# SCH_Well-Pump-Protection-Controller_2025.net
KiCad netlist of a schematic drawn in EasyEDA
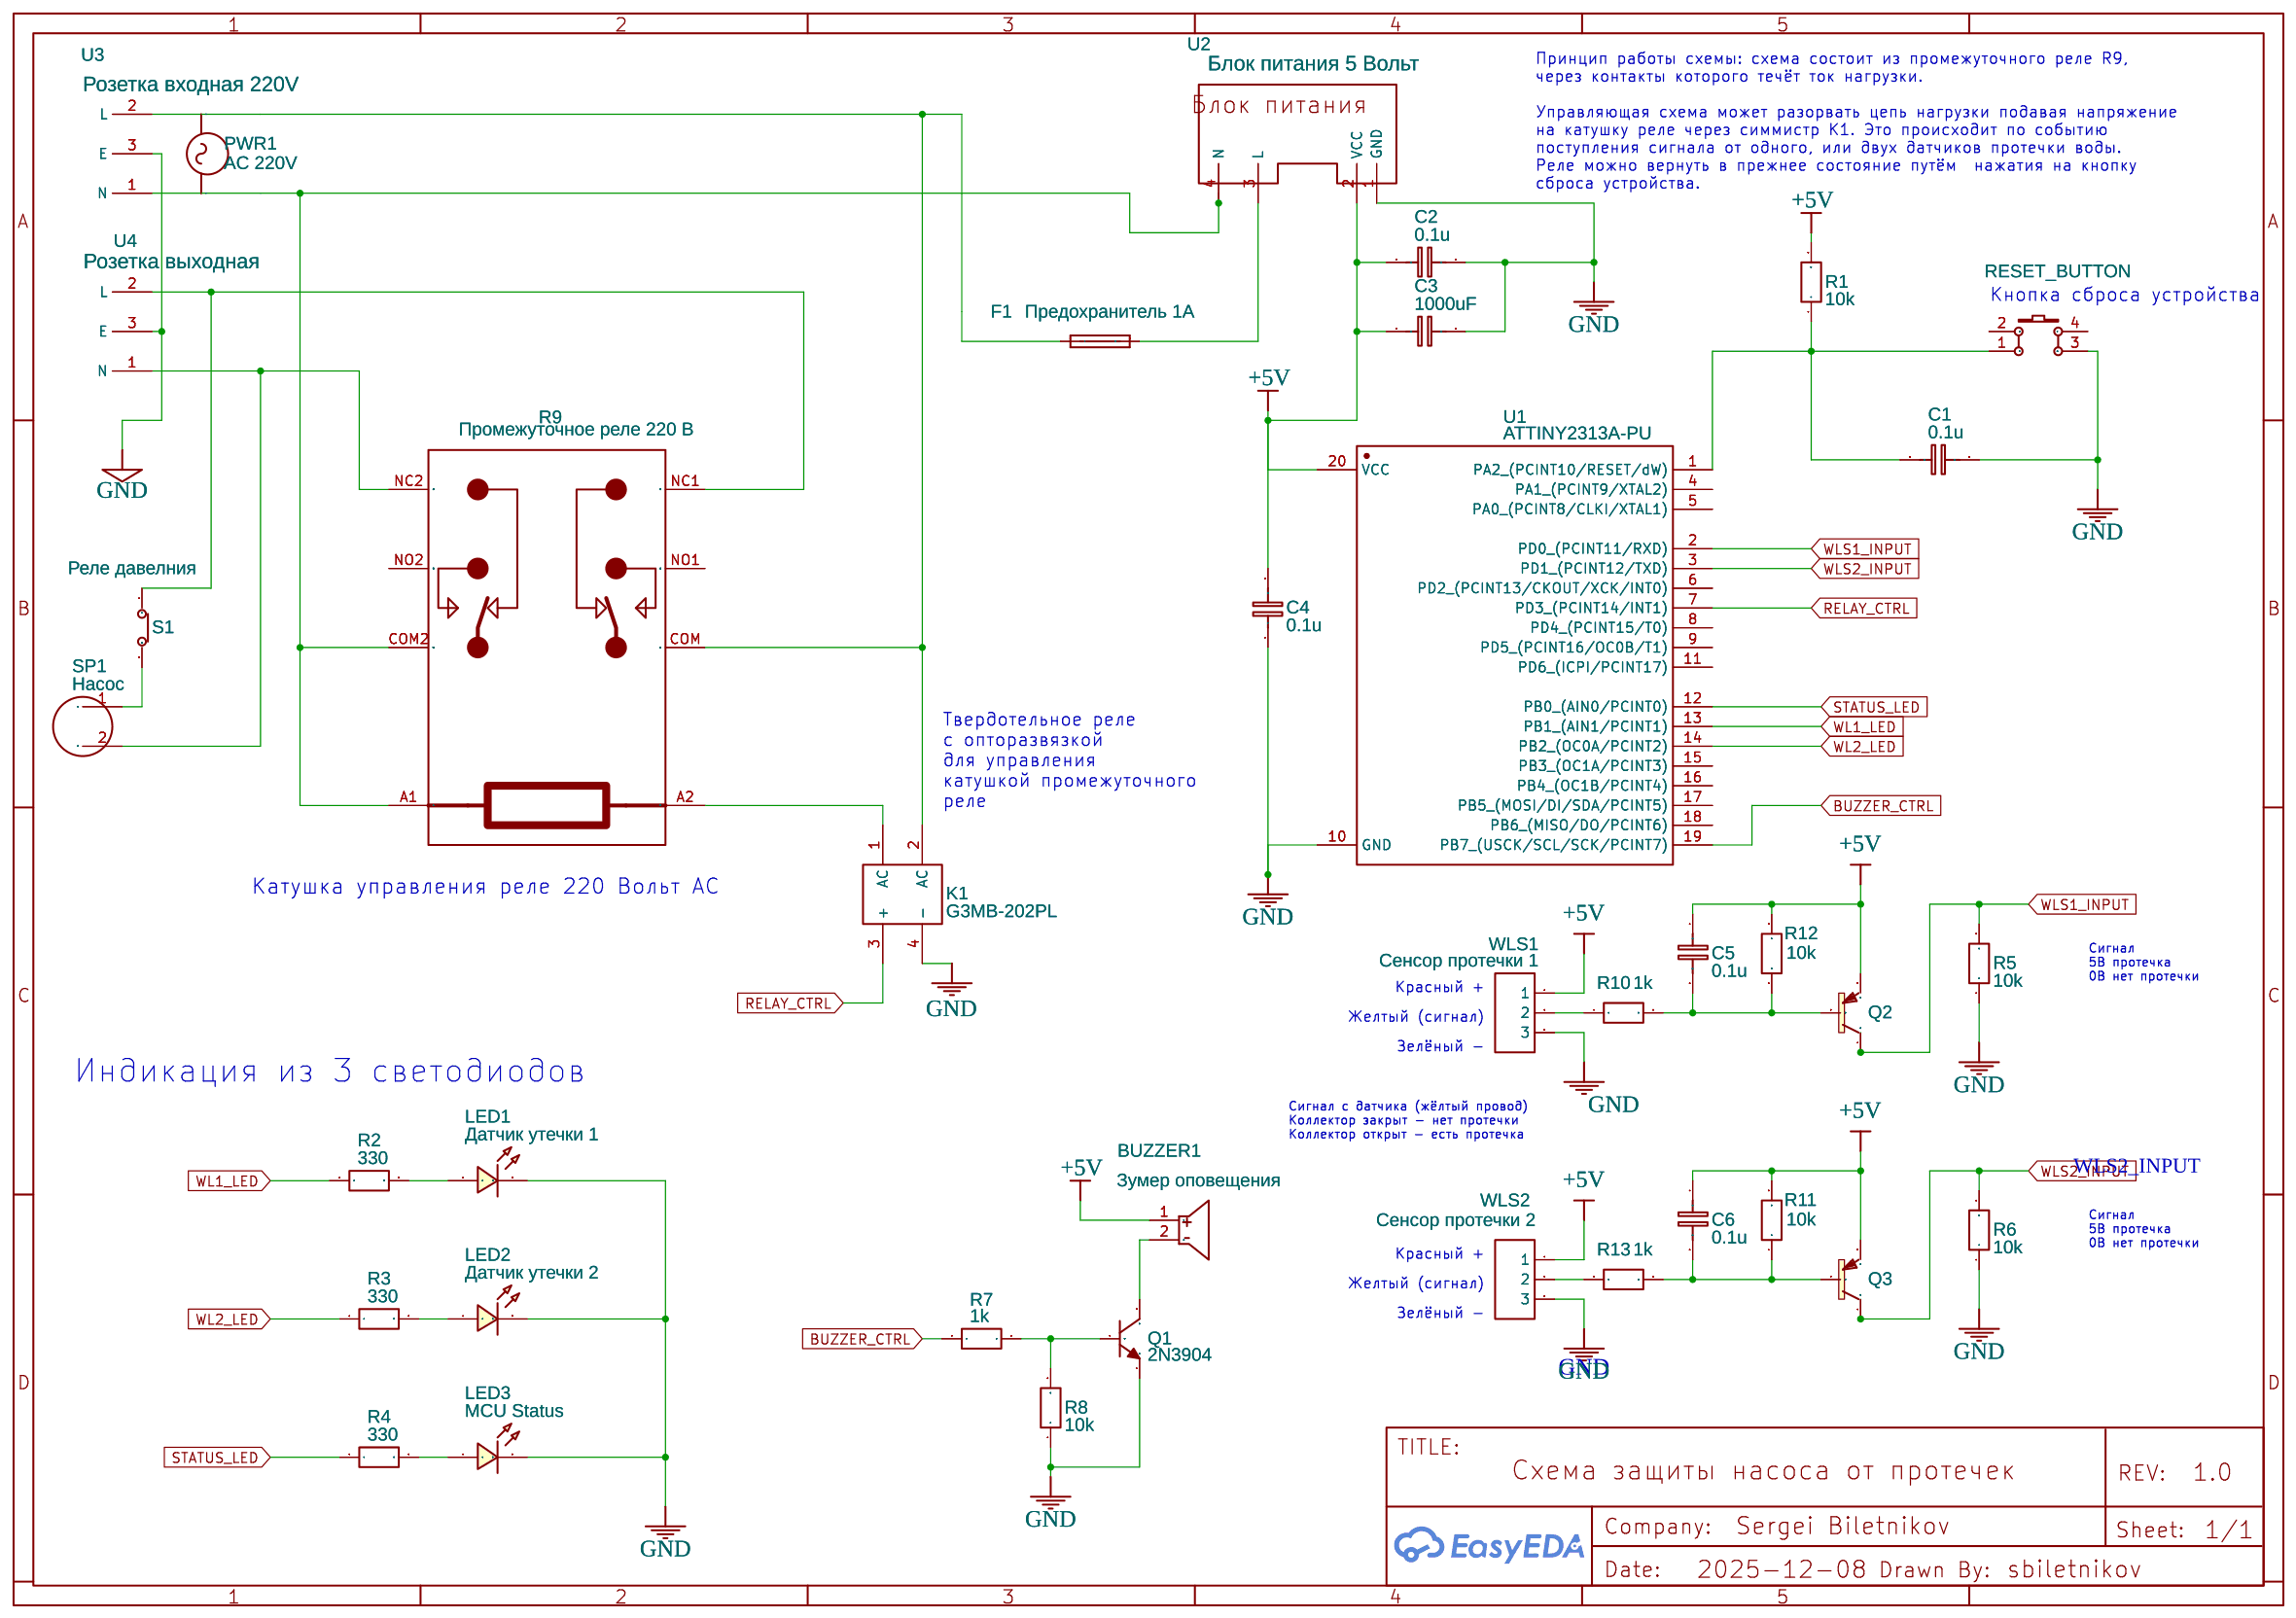
[diagram p0: schematic sheet]

(export (version "E")
  (design (tool "Eeschema 10.0.6"))
  (components
    (comp (ref "BUZZER1")
      (value "Зумер оповещения")
      (fields (field (name "Manufacturer Part") "FMQ-BUZZER2"))
      (libsource (lib "") (part "FMQ-BUZZER2"))
    )
    (comp (ref "C1") (value "0.1u") (libsource (lib "") (part "C_0603_EU")))
    (comp (ref "C2") (value "0.1u") (libsource (lib "") (part "C_0603_EU")))
    (comp (ref "C3") (value "1000uF") (libsource (lib "") (part "C_0603_EU")))
    (comp (ref "C4") (value "0.1u") (libsource (lib "") (part "C_0603_EU_1")))
    (comp (ref "C5") (value "0.1u") (libsource (lib "") (part "C_0603_EU_2")))
    (comp (ref "C6") (value "0.1u") (libsource (lib "") (part "C_0603_EU_2")))
    (comp (ref "F1") (value "Предохранитель 1А") (libsource (lib "") (part "FUSE_TERM")))
    (comp (ref "K1")
      (value "G3MB-202PL")
      (fields (field (name "Manufacturer") "OMRON(欧姆龙)"))
      (libsource (lib "") (part "G3MB-202PL"))
    )
    (comp (ref "LED1")
      (value "Датчик утечки 1")
      (fields
        (field (name "Manufacturer Part") "204-10SDRD/S530-A3-L")
        (field (name "Manufacturer") "EVERLIGHT(台湾亿光)")
      )
      (libsource (lib "") (part "LED-TH-3mm_R"))
    )
    (comp (ref "LED2")
      (value "Датчик утечки 2")
      (fields
        (field (name "Manufacturer Part") "204-10SDRD/S530-A3-L")
        (field (name "Manufacturer") "EVERLIGHT(台湾亿光)")
      )
      (libsource (lib "") (part "LED-TH-3mm_R"))
    )
    (comp (ref "LED3")
      (value "MCU Status")
      (fields
        (field (name "Manufacturer Part") "204-10SYGD/S530-E3")
        (field (name "Manufacturer") "EVERLIGHT(台湾亿光)")
      )
      (libsource (lib "") (part "LED-TH-3mm_G"))
    )
    (comp (ref "PWR1") (value "AC 220V") (libsource (lib "") (part "AC")))
    (comp (ref "Q1")
      (value "2N3904")
      (fields (field (name "Manufacturer Part") "2N3904-338") (field (name "Manufacturer") "ALJ(龙晶微)"))
      (libsource (lib "") (part "2N3904-338"))
    )
    (comp (ref "Q2") (value "2N3906PNP") (libsource (lib "") (part "2N3906PNP")))
    (comp (ref "Q3") (value "2N3906PNP") (libsource (lib "") (part "2N3906PNP")))
    (comp (ref "R1") (value "10k") (libsource (lib "") (part "R_0603_EU")))
    (comp (ref "R2") (value "330") (libsource (lib "") (part "R_0603_EU_1")))
    (comp (ref "R3") (value "330") (libsource (lib "") (part "R_0603_EU_1")))
    (comp (ref "R4") (value "330") (libsource (lib "") (part "R_0603_EU_1")))
    (comp (ref "R5") (value "10k") (libsource (lib "") (part "R_0603_EU")))
    (comp (ref "R6") (value "10k") (libsource (lib "") (part "R_0603_EU")))
    (comp (ref "R7") (value "1k") (libsource (lib "") (part "R_0603_EU_1")))
    (comp (ref "R8") (value "10k") (libsource (lib "") (part "R_0603_EU")))
    (comp (ref "R9")
      (value "Промежуточное реле 220 В")
      (fields (field (name "Manufacturer Part") "RELAY 220V AC COIL"))
      (libsource (lib "") (part "RELAY 220V AC COIL"))
    )
    (comp (ref "R10") (value "1k") (libsource (lib "") (part "R_0603_EU_1")))
    (comp (ref "R11") (value "10k") (libsource (lib "") (part "R_0603_EU")))
    (comp (ref "R12") (value "10k") (libsource (lib "") (part "R_0603_EU")))
    (comp (ref "R13") (value "1k") (libsource (lib "") (part "R_0603_EU_1")))
    (comp (ref "RESET_BUTTON")
      (value "K4-6×6_TH")
      (fields (field (name "Manufacturer Part") "K2-1102DP-E4SW-04") (field (name "Manufacturer") "韩国韩荣"))
      (libsource (lib "") (part "K4-6×6_TH"))
    )
    (comp (ref "S1")
      (value "Реле давелния")
      (fields (field (name "Manufacturer Part") "DIP switchEI-08") (field (name "Manufacturer") "DIP"))
      (libsource (lib "") (part "switch1"))
    )
    (comp (ref "SP1") (value "Насос") (libsource (lib "") (part "Pump buzz")))
    (comp (ref "U1")
      (value "ATTINY2313A-PU")
      (fields (field (name "Manufacturer") "MICROCHIP(美国微芯)"))
      (libsource (lib "") (part "ATTINY2313A-PU"))
    )
    (comp (ref "U2")
      (value "Блок питания 5 Вольт")
      (fields (field (name "Manufacturer Part") "PS-5V"))
      (libsource (lib "") (part "PowerSupply-5v"))
    )
    (comp (ref "U3")
      (value "Розетка входная 220V")
      (fields (field (name "Manufacturer Part") "IEC 320-C14"))
      (libsource (lib "") (part "Power Socket"))
    )
    (comp (ref "U4")
      (value "Розетка выходная")
      (fields (field (name "Manufacturer Part") "IEC 320-C14"))
      (libsource (lib "") (part "Power Socket"))
    )
    (comp (ref "WLS1") (value "Сенсор протечки 1") (libsource (lib "") (part "HDR-F-2.54_1x3")))
    (comp (ref "WLS2") (value "Сенсор протечки 2") (libsource (lib "") (part "HDR-F-2.54_1x3")))
  )
  (nets
    (net (code "1") (name "+5V") (class "Default")
      (node (ref "BUZZER1") (pin "1") (pinfunction "1_1") (pintype "unspecified"))
      (node (ref "C2") (pin "1") (pinfunction "1_1") (pintype "unspecified"))
      (node (ref "C3") (pin "1") (pinfunction "1_1") (pintype "unspecified"))
      (node (ref "C4") (pin "2") (pinfunction "2_2") (pintype "unspecified"))
      (node (ref "C5") (pin "1") (pinfunction "1_1") (pintype "unspecified"))
      (node (ref "C6") (pin "1") (pinfunction "1_1") (pintype "unspecified"))
      (node (ref "Q2") (pin "3") (pinfunction "E_3") (pintype "bidirectional"))
      (node (ref "Q3") (pin "3") (pinfunction "E_3") (pintype "bidirectional"))
      (node (ref "R1") (pin "2") (pinfunction "2_2") (pintype "unspecified"))
      (node (ref "R11") (pin "2") (pinfunction "2_2") (pintype "unspecified"))
      (node (ref "R12") (pin "2") (pinfunction "2_2") (pintype "unspecified"))
      (node (ref "U1") (pin "20") (pinfunction "VCC_20") (pintype "passive"))
      (node (ref "U2") (pin "2") (pinfunction "VCC_2") (pintype "unspecified"))
      (node (ref "WLS1") (pin "1") (pinfunction "1_1") (pintype "input"))
      (node (ref "WLS2") (pin "1") (pinfunction "1_1") (pintype "input"))
    )
    (net (code "2") (name "BUZZER_CTRL") (class "Default")
      (node (ref "R7") (pin "1") (pinfunction "1_1") (pintype "unspecified"))
      (node (ref "U1") (pin "19") (pinfunction "PB7_(USCK/SCL/SCK/PCINT7)_19") (pintype "bidirectional"))
    )
    (net (code "3") (name "GND") (class "Default")
      (node (ref "C1") (pin "2") (pinfunction "2_2") (pintype "unspecified"))
      (node (ref "C2") (pin "2") (pinfunction "2_2") (pintype "unspecified"))
      (node (ref "C3") (pin "2") (pinfunction "2_2") (pintype "unspecified"))
      (node (ref "C4") (pin "1") (pinfunction "1_1") (pintype "unspecified"))
      (node (ref "K1") (pin "4") (pinfunction "-_4") (pintype "unspecified"))
      (node (ref "LED1") (pin "2") (pinfunction "2_2") (pintype "unspecified"))
      (node (ref "LED2") (pin "2") (pinfunction "2_2") (pintype "unspecified"))
      (node (ref "LED3") (pin "2") (pinfunction "2_2") (pintype "unspecified"))
      (node (ref "Q1") (pin "1") (pinfunction "E_1") (pintype "input"))
      (node (ref "R5") (pin "1") (pinfunction "1_1") (pintype "unspecified"))
      (node (ref "R6") (pin "1") (pinfunction "1_1") (pintype "unspecified"))
      (node (ref "R8") (pin "1") (pinfunction "1_1") (pintype "unspecified"))
      (node (ref "RESET_BUTTON") (pin "3") (pinfunction "3_3") (pintype "unspecified"))
      (node (ref "U1") (pin "10") (pinfunction "GND_10") (pintype "passive"))
      (node (ref "U2") (pin "1") (pinfunction "GND_1") (pintype "unspecified"))
      (node (ref "U3") (pin "3") (pinfunction "E_3") (pintype "unspecified"))
      (node (ref "U4") (pin "3") (pinfunction "E_3") (pintype "unspecified"))
      (node (ref "WLS1") (pin "3") (pinfunction "3_3") (pintype "input"))
      (node (ref "WLS2") (pin "3") (pinfunction "3_3") (pintype "input"))
    )
    (net (code "4") (name "Net-(LED1-Pad1)") (class "Default")
      (node (ref "LED1") (pin "1") (pinfunction "1_1") (pintype "unspecified"))
      (node (ref "R2") (pin "2") (pinfunction "2_2") (pintype "unspecified"))
    )
    (net (code "5") (name "Net-(LED2-Pad1)") (class "Default")
      (node (ref "LED2") (pin "1") (pinfunction "1_1") (pintype "unspecified"))
      (node (ref "R3") (pin "2") (pinfunction "2_2") (pintype "unspecified"))
    )
    (net (code "6") (name "Net-(LED3-Pad1)") (class "Default")
      (node (ref "LED3") (pin "1") (pinfunction "1_1") (pintype "unspecified"))
      (node (ref "R4") (pin "2") (pinfunction "2_2") (pintype "unspecified"))
    )
    (net (code "7") (name "Net-(Q1-B)") (class "Default")
      (node (ref "Q1") (pin "2") (pinfunction "B_2") (pintype "input"))
      (node (ref "R7") (pin "2") (pinfunction "2_2") (pintype "unspecified"))
      (node (ref "R8") (pin "2") (pinfunction "2_2") (pintype "unspecified"))
    )
    (net (code "8") (name "Net-(Q1-C)") (class "Default")
      (node (ref "BUZZER1") (pin "2") (pinfunction "2_2") (pintype "unspecified"))
      (node (ref "Q1") (pin "3") (pinfunction "C_3") (pintype "input"))
    )
    (net (code "9") (name "Net-(Q2-B)") (class "Default")
      (node (ref "C5") (pin "2") (pinfunction "2_2") (pintype "unspecified"))
      (node (ref "Q2") (pin "2") (pinfunction "B_2") (pintype "bidirectional"))
      (node (ref "R10") (pin "2") (pinfunction "2_2") (pintype "unspecified"))
      (node (ref "R12") (pin "1") (pinfunction "1_1") (pintype "unspecified"))
    )
    (net (code "10") (name "Net-(Q3-B)") (class "Default")
      (node (ref "C6") (pin "2") (pinfunction "2_2") (pintype "unspecified"))
      (node (ref "Q3") (pin "2") (pinfunction "B_2") (pintype "bidirectional"))
      (node (ref "R11") (pin "1") (pinfunction "1_1") (pintype "unspecified"))
      (node (ref "R13") (pin "2") (pinfunction "2_2") (pintype "unspecified"))
    )
    (net (code "11") (name "Net-(R9-13)") (class "Default")
      (node (ref "K1") (pin "1") (pinfunction "AC_1") (pintype "unspecified"))
      (node (ref "R9") (pin "A2") (pinfunction "13_A2") (pintype "unspecified"))
    )
    (net (code "12") (name "Net-(R9-14)") (class "Default")
      (node (ref "R9") (pin "A1") (pinfunction "14_A1") (pintype "unspecified"))
      (node (ref "R9") (pin "COM2") (pinfunction "COM2_COM2") (pintype "unspecified"))
      (node (ref "U2") (pin "4") (pinfunction "N_4") (pintype "unspecified"))
      (node (ref "U3") (pin "1") (pinfunction "N_1") (pintype "unspecified"))
    )
    (net (code "13") (name "Net-(R10-Pad1)") (class "Default")
      (node (ref "R10") (pin "1") (pinfunction "1_1") (pintype "unspecified"))
      (node (ref "WLS1") (pin "2") (pinfunction "2_2") (pintype "input"))
    )
    (net (code "14") (name "Net-(R13-Pad1)") (class "Default")
      (node (ref "R13") (pin "1") (pinfunction "1_1") (pintype "unspecified"))
      (node (ref "WLS2") (pin "2") (pinfunction "2_2") (pintype "input"))
    )
    (net (code "15") (name "Net-(S1-Pad3)") (class "Default")
      (node (ref "S1") (pin "3") (pinfunction "3_3") (pintype "unspecified"))
      (node (ref "SP1") (pin "1") (pinfunction "1_1") (pintype "unspecified"))
    )
    (net (code "16") (name "Net-(U1-PA2_(PCINT10{slash}RESET{slash}dW))") (class "Default")
      (node (ref "C1") (pin "1") (pinfunction "1_1") (pintype "unspecified"))
      (node (ref "R1") (pin "1") (pinfunction "1_1") (pintype "unspecified"))
      (node (ref "RESET_BUTTON") (pin "1") (pinfunction "1_1") (pintype "unspecified"))
      (node (ref "U1") (pin "1") (pinfunction "PA2_(PCINT10/RESET/dW)_1") (pintype "bidirectional"))
    )
    (net (code "17") (name "Net-(U2-L)") (class "Default")
      (node (ref "F1") (pin "2") (pinfunction "2_2") (pintype "bidirectional"))
      (node (ref "U2") (pin "3") (pinfunction "L_3") (pintype "unspecified"))
    )
    (net (code "18") (name "Net-(U3-L)") (class "Default")
      (node (ref "F1") (pin "1") (pinfunction "1_1") (pintype "bidirectional"))
      (node (ref "K1") (pin "2") (pinfunction "AC_2") (pintype "unspecified"))
      (node (ref "R9") (pin "COM") (pinfunction "COM_COM") (pintype "unspecified"))
      (node (ref "U3") (pin "2") (pinfunction "L_2") (pintype "unspecified"))
    )
    (net (code "19") (name "Net-(U4-L)") (class "Default")
      (node (ref "R9") (pin "NC1") (pinfunction "NC1_NC1") (pintype "unspecified"))
      (node (ref "S1") (pin "4") (pinfunction "4_4") (pintype "unspecified"))
      (node (ref "U4") (pin "2") (pinfunction "L_2") (pintype "unspecified"))
    )
    (net (code "20") (name "Net-(U4-N)") (class "Default")
      (node (ref "R9") (pin "NC2") (pinfunction "NO2_NC2") (pintype "unspecified"))
      (node (ref "SP1") (pin "2") (pinfunction "2_2") (pintype "unspecified"))
      (node (ref "U4") (pin "1") (pinfunction "N_1") (pintype "unspecified"))
    )
    (net (code "21") (name "RELAY_CTRL") (class "Default")
      (node (ref "K1") (pin "3") (pinfunction "+_3") (pintype "unspecified"))
      (node (ref "U1") (pin "7") (pinfunction "PD3_(PCINT14/INT1)_7") (pintype "bidirectional"))
    )
    (net (code "22") (name "STATUS_LED") (class "Default")
      (node (ref "R4") (pin "1") (pinfunction "1_1") (pintype "unspecified"))
      (node (ref "U1") (pin "12") (pinfunction "PB0_(AIN0/PCINT0)_12") (pintype "bidirectional"))
    )
    (net (code "23") (name "WL1_LED") (class "Default")
      (node (ref "R2") (pin "1") (pinfunction "1_1") (pintype "unspecified"))
      (node (ref "U1") (pin "13") (pinfunction "PB1_(AIN1/PCINT1)_13") (pintype "bidirectional"))
    )
    (net (code "24") (name "WL2_LED") (class "Default")
      (node (ref "R3") (pin "1") (pinfunction "1_1") (pintype "unspecified"))
      (node (ref "U1") (pin "14") (pinfunction "PB2_(OC0A/PCINT2)_14") (pintype "bidirectional"))
    )
    (net (code "25") (name "WLS1_INPUT") (class "Default")
      (node (ref "Q2") (pin "1") (pinfunction "C_1") (pintype "bidirectional"))
      (node (ref "R5") (pin "2") (pinfunction "2_2") (pintype "unspecified"))
      (node (ref "U1") (pin "2") (pinfunction "PD0_(PCINT11/RXD)_2") (pintype "bidirectional"))
    )
    (net (code "26") (name "WLS2_INPUT") (class "Default")
      (node (ref "Q3") (pin "1") (pinfunction "C_1") (pintype "bidirectional"))
      (node (ref "R6") (pin "2") (pinfunction "2_2") (pintype "unspecified"))
      (node (ref "U1") (pin "3") (pinfunction "PD1_(PCINT12/TXD)_3") (pintype "bidirectional"))
    )
    (net (code "27") (name "unconnected-(PWR1-Pad+)") (class "Default")
      (node (ref "PWR1") (pin "+") (pinfunction "+_+") (pintype "bidirectional"))
    )
    (net (code "28") (name "unconnected-(PWR1-Pad-)") (class "Default")
      (node (ref "PWR1") (pin "-") (pinfunction "-_-") (pintype "bidirectional"))
    )
    (net (code "29") (name "unconnected-(R9-PadNO1)") (class "Default")
      (node (ref "R9") (pin "NO1") (pinfunction "NO1_NO1") (pintype "unspecified"))
    )
    (net (code "30") (name "unconnected-(R9-PadNO2)") (class "Default")
      (node (ref "R9") (pin "NO2") (pinfunction "NO2_NO2") (pintype "unspecified"))
    )
    (net (code "31") (name "unconnected-(RESET_BUTTON-Pad2)") (class "Default")
      (node (ref "RESET_BUTTON") (pin "2") (pinfunction "2_2") (pintype "unspecified"))
    )
    (net (code "32") (name "unconnected-(RESET_BUTTON-Pad4)") (class "Default")
      (node (ref "RESET_BUTTON") (pin "4") (pinfunction "4_4") (pintype "unspecified"))
    )
    (net (code "33") (name "unconnected-(U1-PA0_(PCINT8{slash}CLKI{slash}XTAL1)-Pad5)") (class "Default")
      (node (ref "U1") (pin "5") (pinfunction "PA0_(PCINT8/CLKI/XTAL1)_5") (pintype "bidirectional"))
    )
    (net (code "34") (name "unconnected-(U1-PA1_(PCINT9{slash}XTAL2)-Pad4)") (class "Default")
      (node (ref "U1") (pin "4") (pinfunction "PA1_(PCINT9/XTAL2)_4") (pintype "bidirectional"))
    )
    (net (code "35") (name "unconnected-(U1-PB3_(OC1A{slash}PCINT3)-Pad15)") (class "Default")
      (node (ref "U1") (pin "15") (pinfunction "PB3_(OC1A/PCINT3)_15") (pintype "bidirectional"))
    )
    (net (code "36") (name "unconnected-(U1-PB4_(OC1B{slash}PCINT4)-Pad16)") (class "Default")
      (node (ref "U1") (pin "16") (pinfunction "PB4_(OC1B/PCINT4)_16") (pintype "bidirectional"))
    )
    (net (code "37") (name "unconnected-(U1-PB5_(MOSI{slash}DI{slash}SDA{slash}PCINT5)-Pad17)") (class "Default")
      (node (ref "U1") (pin "17") (pinfunction "PB5_(MOSI/DI/SDA/PCINT5)_17") (pintype "bidirectional"))
    )
    (net (code "38") (name "unconnected-(U1-PB6_(MISO{slash}DO{slash}PCINT6)-Pad18)") (class "Default")
      (node (ref "U1") (pin "18") (pinfunction "PB6_(MISO/DO/PCINT6)_18") (pintype "bidirectional"))
    )
    (net (code "39") (name "unconnected-(U1-PD2_(PCINT13{slash}CKOUT{slash}XCK{slash}INT0)-Pad6)") (class "Default")
      (node (ref "U1") (pin "6") (pinfunction "PD2_(PCINT13/CKOUT/XCK/INT0)_6") (pintype "bidirectional"))
    )
    (net (code "40") (name "unconnected-(U1-PD4_(PCINT15{slash}T0)-Pad8)") (class "Default")
      (node (ref "U1") (pin "8") (pinfunction "PD4_(PCINT15/T0)_8") (pintype "bidirectional"))
    )
    (net (code "41") (name "unconnected-(U1-PD5_(PCINT16{slash}OC0B{slash}T1)-Pad9)") (class "Default")
      (node (ref "U1") (pin "9") (pinfunction "PD5_(PCINT16/OC0B/T1)_9") (pintype "bidirectional"))
    )
    (net (code "42") (name "unconnected-(U1-PD6_(ICPI{slash}PCINT17)-Pad11)") (class "Default")
      (node (ref "U1") (pin "11") (pinfunction "PD6_(ICPI/PCINT17)_11") (pintype "bidirectional"))
    )
  )
)
